# US_BB_SH.net
KiCad netlist of a schematic drawn in Altium Designer
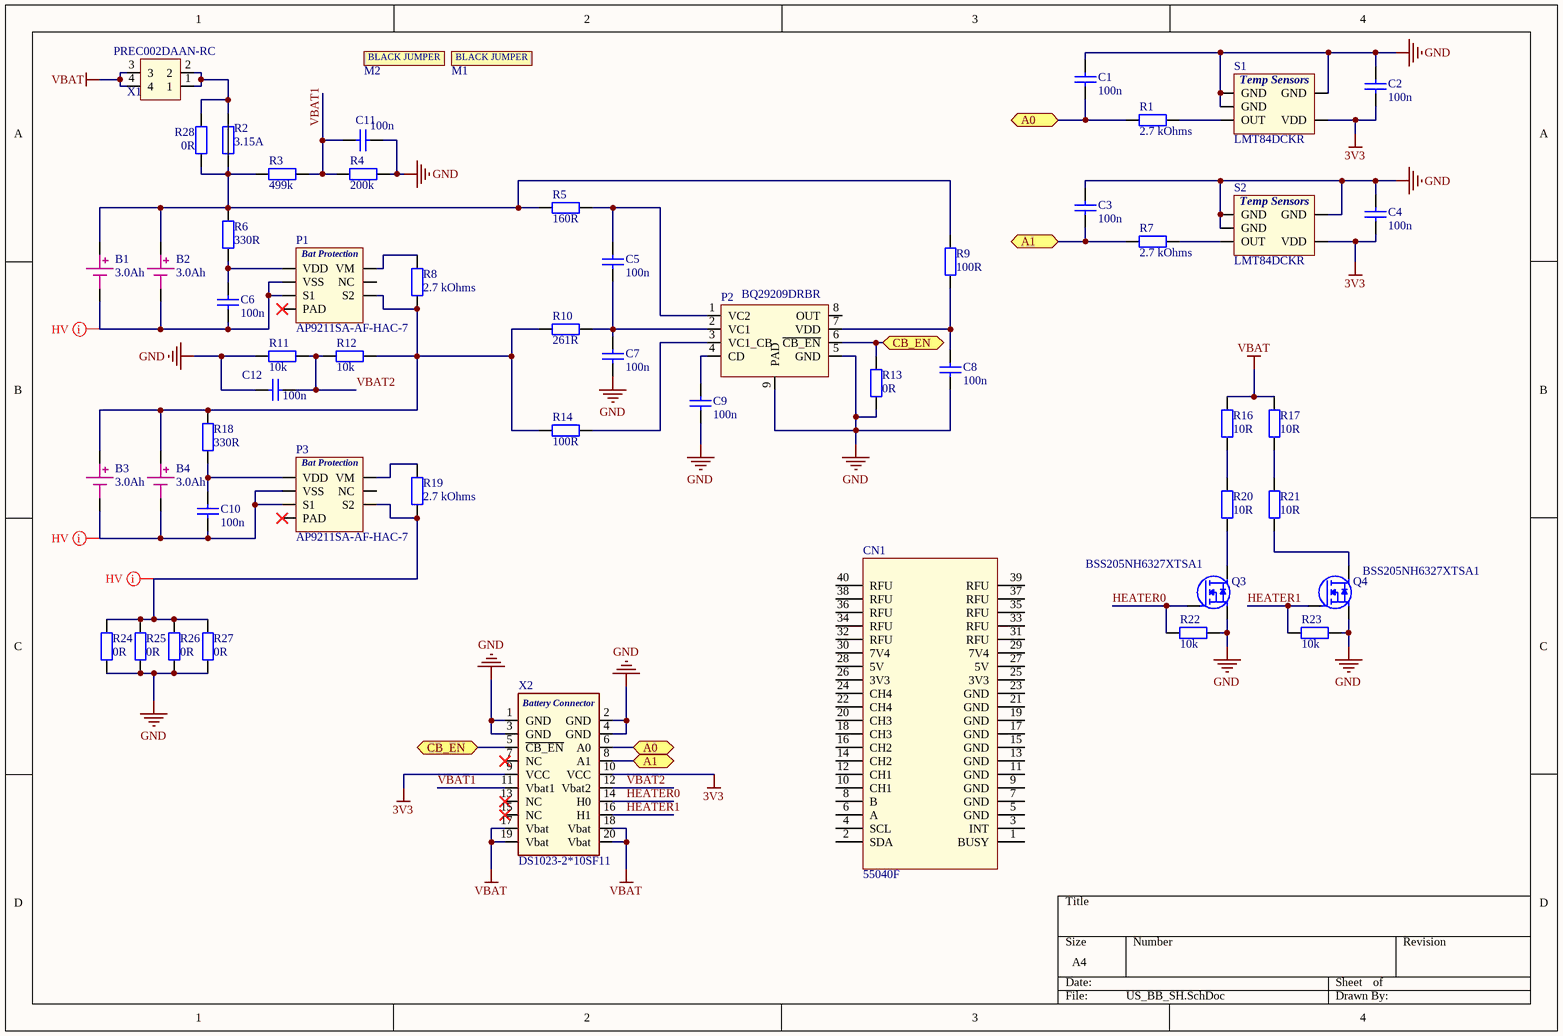
[diagram p0: US_BB_SH.SchDoc]

(export (version "E")
  (design (tool "Eeschema 10.0.6"))
  (components
    (comp (ref "B1")
      (value "3.0Ah")
      (footprint "BAT18650 1S-MSL")
      (description "18650 3.7V Lithium-Ion Battery Rechargeable (Secondary) 2.6Ah")
      (fields
        (field (name "MANUFACTURER") "Litokala")
        (field (name "MANUFACTURER PART NUMBER") "Litokala_HG2")
      )
      (libsource (lib "alfasat_lib_eps") (part "18650 3.7V Li-ion"))
    )
    (comp (ref "B2")
      (value "3.0Ah")
      (footprint "BAT18650 1S-MSL")
      (description "18650 3.7V Lithium-Ion Battery Rechargeable (Secondary) 2.6Ah")
      (fields
        (field (name "MANUFACTURER") "Litokala")
        (field (name "MANUFACTURER PART NUMBER") "Litokala_HG2")
      )
      (libsource (lib "alfasat_lib_eps") (part "18650 3.7V Li-ion"))
    )
    (comp (ref "B3")
      (value "3.0Ah")
      (footprint "BAT18650 1S-MSL")
      (description "18650 3.7V Lithium-Ion Battery Rechargeable (Secondary) 2.6Ah")
      (fields
        (field (name "MANUFACTURER") "Litokala")
        (field (name "MANUFACTURER PART NUMBER") "Litokala_HG2")
      )
      (libsource (lib "alfasat_lib_eps") (part "18650 3.7V Li-ion"))
    )
    (comp (ref "B4")
      (value "3.0Ah")
      (footprint "BAT18650 1S-MSL")
      (description "18650 3.7V Lithium-Ion Battery Rechargeable (Secondary) 2.6Ah")
      (fields
        (field (name "MANUFACTURER") "Litokala")
        (field (name "MANUFACTURER PART NUMBER") "Litokala_HG2")
      )
      (libsource (lib "alfasat_lib_eps") (part "18650 3.7V Li-ion"))
    )
    (comp (ref "C1")
      (value "100n")
      (footprint "C0603_IPC_HD")
      (description "CAP CER 0.1UF 16V X7R 0603")
      (fields
        (field (name "MANUFACTURER") "Samsung Electro-Mechanics")
        (field (name "MANUFACTURER PART NUMBER") "CL10B104KO8NNNC")
      )
      (libsource (lib "alfasat_lib") (part "CL10B104KO8NNNC"))
    )
    (comp (ref "C2")
      (value "100n")
      (footprint "C0603_IPC_HD")
      (description "CAP CER 0.1UF 16V X7R 0603")
      (fields
        (field (name "MANUFACTURER") "Samsung Electro-Mechanics")
        (field (name "MANUFACTURER PART NUMBER") "CL10B104KO8NNNC")
      )
      (libsource (lib "alfasat_lib") (part "CL10B104KO8NNNC"))
    )
    (comp (ref "C3")
      (value "100n")
      (footprint "C0603_IPC_HD")
      (description "CAP CER 0.1UF 16V X7R 0603")
      (fields
        (field (name "MANUFACTURER") "Samsung Electro-Mechanics")
        (field (name "MANUFACTURER PART NUMBER") "CL10B104KO8NNNC")
      )
      (libsource (lib "alfasat_lib") (part "CL10B104KO8NNNC"))
    )
    (comp (ref "C4")
      (value "100n")
      (footprint "C0603_IPC_HD")
      (description "CAP CER 0.1UF 16V X7R 0603")
      (fields
        (field (name "MANUFACTURER") "Samsung Electro-Mechanics")
        (field (name "MANUFACTURER PART NUMBER") "CL10B104KO8NNNC")
      )
      (libsource (lib "alfasat_lib") (part "CL10B104KO8NNNC"))
    )
    (comp (ref "C5")
      (value "100n")
      (footprint "C0603_IPC_HD")
      (description "CAP CER 0.1UF 16V X7R 0603")
      (fields
        (field (name "MANUFACTURER") "Samsung Electro-Mechanics")
        (field (name "MANUFACTURER PART NUMBER") "CL10B104KO8NNNC")
      )
      (libsource (lib "alfasat_lib") (part "CL10B104KO8NNNC"))
    )
    (comp (ref "C6")
      (value "100n")
      (footprint "C0603_IPC_HD")
      (description "CAP CER 0.1UF 16V X7R 0603")
      (fields
        (field (name "MANUFACTURER") "Samsung Electro-Mechanics")
        (field (name "MANUFACTURER PART NUMBER") "CL10B104KO8NNNC")
      )
      (libsource (lib "alfasat_lib") (part "CL10B104KO8NNNC"))
    )
    (comp (ref "C7")
      (value "100n")
      (footprint "C0603_IPC_HD")
      (description "CAP CER 0.1UF 16V X7R 0603")
      (fields
        (field (name "MANUFACTURER") "Samsung Electro-Mechanics")
        (field (name "MANUFACTURER PART NUMBER") "CL10B104KO8NNNC")
      )
      (libsource (lib "alfasat_lib") (part "CL10B104KO8NNNC"))
    )
    (comp (ref "C8")
      (value "100n")
      (footprint "C0603_IPC_HD")
      (description "CAP CER 0.1UF 16V X7R 0603")
      (fields
        (field (name "MANUFACTURER") "Samsung Electro-Mechanics")
        (field (name "MANUFACTURER PART NUMBER") "CL10B104KO8NNNC")
      )
      (libsource (lib "alfasat_lib") (part "CL10B104KO8NNNC"))
    )
    (comp (ref "C9")
      (value "100n")
      (footprint "C0603_IPC_HD")
      (description "CAP CER 0.1UF 16V X7R 0603")
      (fields
        (field (name "MANUFACTURER") "Samsung Electro-Mechanics")
        (field (name "MANUFACTURER PART NUMBER") "CL10B104KO8NNNC")
      )
      (libsource (lib "alfasat_lib") (part "CL10B104KO8NNNC"))
    )
    (comp (ref "C10")
      (value "100n")
      (footprint "C0603_IPC_HD")
      (description "CAP CER 0.1UF 16V X7R 0603")
      (fields
        (field (name "MANUFACTURER") "Samsung Electro-Mechanics")
        (field (name "MANUFACTURER PART NUMBER") "CL10B104KO8NNNC")
      )
      (libsource (lib "alfasat_lib") (part "CL10B104KO8NNNC"))
    )
    (comp (ref "C11")
      (value "100n")
      (footprint "C0603_IPC_HD")
      (description "CAP CER 0.1UF 16V X7R 0603")
      (fields
        (field (name "MANUFACTURER") "Samsung Electro-Mechanics")
        (field (name "MANUFACTURER PART NUMBER") "CL10B104KO8NNNC")
      )
      (libsource (lib "alfasat_parts_lib") (part "CL10B104KO8NNNC"))
    )
    (comp (ref "C12")
      (value "100n")
      (footprint "C0603_IPC_HD")
      (description "CAP CER 0.1UF 16V X7R 0603")
      (fields
        (field (name "MANUFACTURER") "Samsung Electro-Mechanics")
        (field (name "MANUFACTURER PART NUMBER") "CL10B104KO8NNNC")
      )
      (libsource (lib "alfasat_parts_lib") (part "CL10B104KO8NNNC"))
    )
    (comp (ref "CN1")
      (value "55040F")
      (footprint "HEADER_40PIN_12MM2")
      (description "CONN HEADER R/A 40POS 2.54MM")
      (fields (field (name "MANUFACTURER") "On Shore Technology Inc."))
      (libsource (lib "alfasat_lib") (part "ALFASAT_BIC"))
    )
    (comp (ref "M1")
      (value "STC02SYAN")
      (description "CONN JUMPER SHORTING TIN")
      (fields (field (name "MANUFACTURER") "Sullins Connector Solutions"))
      (libsource (lib "alfasat_lib") (part "STC02SYAN"))
    )
    (comp (ref "M2")
      (value "STC02SYAN")
      (description "CONN JUMPER SHORTING TIN")
      (fields (field (name "MANUFACTURER") "Sullins Connector Solutions"))
      (libsource (lib "alfasat_lib") (part "STC02SYAN"))
    )
    (comp (ref "P1")
      (value "AP9211SA-AF-HAC-7")
      (footprint "U-DFN2030-6 (Type C)")
      (description "Battery Battery Protection IC Lithium-Ion U-DFN2030-6 (Type C)")
      (fields (field (name "MANUFACTURER") "Diodes Incorporated"))
      (libsource (lib "alfasat_lib_eps") (part "AP9211SA-AF"))
    )
    (comp (ref "P2")
      (value "BQ29209DRBR")
      (footprint "alfasat_lib_eps:bq29209_SON65P300X100_HS-9N")
      (description "Battery Battery Protection IC Lithium-Ion 8-SON (3x3)")
      (fields (field (name "MANUFACTURER") "Texas Instruments"))
      (libsource (lib "alfasat_lib_eps") (part "BQ29209DRBR"))
    )
    (comp (ref "P3")
      (value "AP9211SA-AF-HAC-7")
      (footprint "U-DFN2030-6 (Type C)")
      (description "Battery Battery Protection IC Lithium-Ion U-DFN2030-6 (Type C)")
      (fields (field (name "MANUFACTURER") "Diodes Incorporated"))
      (libsource (lib "alfasat_lib_eps") (part "AP9211SA-AF"))
    )
    (comp (ref "Q3")
      (value "BSS205NH6327XTSA1")
      (footprint "SOT23")
      (description "N-Channel 20V 2.5A (Ta) 500mW (Ta) Surface Mount SOT-23-3")
      (fields (field (name "MANUFACTURER") "Infineon Technologies"))
      (libsource (lib "alfasat_lib_eps") (part "BSS205NH6327XTSA1"))
    )
    (comp (ref "Q4")
      (value "BSS205NH6327XTSA1")
      (footprint "SOT23")
      (description "N-Channel 20V 2.5A (Ta) 500mW (Ta) Surface Mount SOT-23-3")
      (fields (field (name "MANUFACTURER") "Infineon Technologies"))
      (libsource (lib "alfasat_lib_eps") (part "BSS205NH6327XTSA1"))
    )
    (comp (ref "R1")
      (value "2.7 kOhms")
      (footprint "alfasat_lib_eps:C0805_IPC_HD")
      (description "RES 2.7K OHM 1% 1/8W 0805")
      (fields
        (field (name "MANUFACTURER") "Stackpole Electronics Inc")
        (field (name "MANUFACTURER PART NUMBER") "RMCF0805FT2K70")
      )
      (libsource (lib "") (part "CR0805_RMC_2.7k_1"))
    )
    (comp (ref "R2")
      (value "3.15A")
      (footprint "alfasat_lib_eps:C0603_IPC_MD")
      (description "FUSE BOARD MNT 3.15A 32VDC 0603")
      (fields
        (field (name "MANUFACTURER") "Panasonic Electronic Components")
        (field (name "MANUFACTURER PART NUMBER") "ERB-RE3R15V")
      )
      (libsource (lib "alfasat_lib_eps") (part "CR0603_3A15"))
    )
    (comp (ref "R3")
      (value "499k")
      (footprint "alfasat_lib_eps:C0603_IPC_HD")
      (description "RES 499K OHM 1% 1/10W 0603")
      (fields
        (field (name "MANUFACTURER") "Stackpole Electronics Inc")
        (field (name "MANUFACTURER PART NUMBER") "RMCF0603FT499K")
      )
      (libsource (lib "alfasat_lib_eps") (part "CR0603-JW-499K"))
    )
    (comp (ref "R4")
      (value "200k")
      (footprint "alfasat_lib_eps:C0603_IPC_HD")
      (description "RES 200K OHM 1% 1/10W 0603")
      (fields
        (field (name "MANUFACTURER") "Stackpole Electronics Inc")
        (field (name "MANUFACTURER PART NUMBER") "RMCF0603FT200K")
      )
      (libsource (lib "alfasat_lib_eps") (part "CR0603-JW-200k"))
    )
    (comp (ref "R5")
      (value "160R")
      (footprint "C0805_IPC_HD")
      (description "RES SMD 160 OHM 1% 1/8W 0805")
      (fields
        (field (name "MANUFACTURER") "Rohm Semiconductor")
        (field (name "MANUFACTURER PART NUMBER") "MCR10ERTF1600")
      )
      (libsource (lib "alfasat_lib_eps") (part "CR0805_RMC_160R"))
    )
    (comp (ref "R6")
      (value "330R")
      (footprint "alfasat_lib_eps:C0805_IPC_HD")
      (description "RES 330 OHM 1% 1/8W 0805")
      (fields
        (field (name "MANUFACTURER") "Stackpole Electronics Inc")
        (field (name "MANUFACTURER PART NUMBER") "RMCF0805FT330R")
      )
      (libsource (lib "alfasat_lib_eps") (part "CR0805_RMC_330R"))
    )
    (comp (ref "R7")
      (value "2.7 kOhms")
      (footprint "alfasat_lib_eps:C0805_IPC_HD")
      (description "RES 2.7K OHM 1% 1/8W 0805")
      (fields
        (field (name "MANUFACTURER") "Stackpole Electronics Inc")
        (field (name "MANUFACTURER PART NUMBER") "RMCF0805FT2K70")
      )
      (libsource (lib "") (part "CR0805_RMC_2.7k_1"))
    )
    (comp (ref "R8")
      (value "2.7 kOhms")
      (footprint "alfasat_lib_eps:C0805_IPC_HD")
      (description "RES 2.7K OHM 1% 1/8W 0805")
      (fields
        (field (name "MANUFACTURER") "Stackpole Electronics Inc")
        (field (name "MANUFACTURER PART NUMBER") "RMCF0805FT2K70")
      )
      (libsource (lib "alfasat_lib_eps") (part "CR0805_RMC_2.7k"))
    )
    (comp (ref "R9")
      (value "100R")
      (footprint "R0805_IPC_MD")
      (description "RES 100 OHM 1% 1/8W 0805")
      (fields
        (field (name "MANUFACTURER") "Stackpole Electronics Inc")
        (field (name "MANUFACTURER PART NUMBER") "RMCF0805FT100R")
      )
      (libsource (lib "alfasat_lib_eps") (part "CR0805_RMC1_100R"))
    )
    (comp (ref "R10")
      (value "261R")
      (footprint "C0805_IPC_HD")
      (description "RES SMD 261 OHM 1% 1/8W 0805")
      (fields
        (field (name "MANUFACTURER") "Rohm Semiconductor")
        (field (name "MANUFACTURER PART NUMBER") "MCR10ERTF2610")
      )
      (libsource (lib "alfasat_lib_eps") (part "CR0805_RMC_261R"))
    )
    (comp (ref "R11")
      (value "10k")
      (footprint "C0603_IPC_HD")
      (description "RES 10K OHM 1% 1/10W 0603")
      (fields
        (field (name "MANUFACTURER") "Stackpole Electronics Inc")
        (field (name "MANUFACTURER PART NUMBER") "RMCF0603FT10K0")
      )
      (libsource (lib "alfasat_lib_eps") (part "CR0603-JW-10k"))
    )
    (comp (ref "R12")
      (value "10k")
      (footprint "C0603_IPC_HD")
      (description "RES 10K OHM 1% 1/10W 0603")
      (fields
        (field (name "MANUFACTURER") "Stackpole Electronics Inc")
        (field (name "MANUFACTURER PART NUMBER") "RMCF0603FT10K0")
      )
      (libsource (lib "alfasat_lib_eps") (part "CR0603-JW-10k"))
    )
    (comp (ref "R13")
      (value "0R")
      (footprint "R0603_IPC_MD")
      (description "RES SMD 0 OHM JUMPER 1/10W 0603")
      (fields
        (field (name "MANUFACTURER") "Bourns Inc.")
        (field (name "MANUFACTURER PART NUMBER") "CR0603-J/-000ELF")
      )
      (libsource (lib "alfasat_lib") (part "CR0603-J/-000ELF"))
    )
    (comp (ref "R14")
      (value "100R")
      (footprint "R0805_IPC_MD")
      (description "RES 100 OHM 1% 1/8W 0805")
      (fields
        (field (name "MANUFACTURER") "Stackpole Electronics Inc")
        (field (name "MANUFACTURER PART NUMBER") "RMCF0805FT100R")
      )
      (libsource (lib "") (part "CR0805_RMC1_100R_1"))
    )
    (comp (ref "R16")
      (value "10R")
      (footprint "alfasat_lib_eps:FMP300JT-73-10R")
      (description "RES 10 OHM 3W 5% AXIAL")
      (fields
        (field (name "MANUFACTURER") "Yageo")
        (field (name "MANUFACTURER PART NUMBER") "FMP300JT-73-10R")
      )
      (libsource (lib "alfasat_lib_eps") (part "FMP300JT-73-10R"))
    )
    (comp (ref "R17")
      (value "10R")
      (footprint "alfasat_lib_eps:FMP300JT-73-10R")
      (description "RES 10 OHM 3W 5% AXIAL")
      (fields
        (field (name "MANUFACTURER") "Yageo")
        (field (name "MANUFACTURER PART NUMBER") "FMP300JT-73-10R")
      )
      (libsource (lib "alfasat_lib_eps") (part "FMP300JT-73-10R"))
    )
    (comp (ref "R18")
      (value "330R")
      (footprint "alfasat_lib_eps:C0805_IPC_HD")
      (description "RES 330 OHM 1% 1/8W 0805")
      (fields
        (field (name "MANUFACTURER") "Stackpole Electronics Inc")
        (field (name "MANUFACTURER PART NUMBER") "RMCF0805FT330R")
      )
      (libsource (lib "alfasat_lib_eps") (part "CR0805_RMC_330R"))
    )
    (comp (ref "R19")
      (value "2.7 kOhms")
      (footprint "alfasat_lib_eps:C0805_IPC_HD")
      (description "RES 2.7K OHM 1% 1/8W 0805")
      (fields
        (field (name "MANUFACTURER") "Stackpole Electronics Inc")
        (field (name "MANUFACTURER PART NUMBER") "RMCF0805FT2K70")
      )
      (libsource (lib "alfasat_lib_eps") (part "CR0805_RMC_2.7k"))
    )
    (comp (ref "R20")
      (value "10R")
      (footprint "alfasat_lib_eps:FMP300JT-73-10R")
      (description "RES 10 OHM 3W 5% AXIAL")
      (fields
        (field (name "MANUFACTURER") "Yageo")
        (field (name "MANUFACTURER PART NUMBER") "FMP300JT-73-10R")
      )
      (libsource (lib "alfasat_lib_eps") (part "FMP300JT-73-10R"))
    )
    (comp (ref "R21")
      (value "10R")
      (footprint "alfasat_lib_eps:FMP300JT-73-10R")
      (description "RES 10 OHM 3W 5% AXIAL")
      (fields
        (field (name "MANUFACTURER") "Yageo")
        (field (name "MANUFACTURER PART NUMBER") "FMP300JT-73-10R")
      )
      (libsource (lib "alfasat_lib_eps") (part "FMP300JT-73-10R"))
    )
    (comp (ref "R22")
      (value "10k")
      (footprint "C0603_IPC_HD")
      (description "RES 10K OHM 1% 1/10W 0603")
      (fields
        (field (name "MANUFACTURER") "Stackpole Electronics Inc")
        (field (name "MANUFACTURER PART NUMBER") "RMCF0603FT10K0")
      )
      (libsource (lib "") (part "CR0603-JW-10k_1"))
    )
    (comp (ref "R23")
      (value "10k")
      (footprint "C0603_IPC_HD")
      (description "RES 10K OHM 1% 1/10W 0603")
      (fields
        (field (name "MANUFACTURER") "Stackpole Electronics Inc")
        (field (name "MANUFACTURER PART NUMBER") "RMCF0603FT10K0")
      )
      (libsource (lib "alfasat_lib_eps") (part "CR0603-JW-10k"))
    )
    (comp (ref "R24")
      (value "0R")
      (footprint "R0603_IPC_MD")
      (description "RES SMD 0 OHM JUMPER 1/10W 0603")
      (fields
        (field (name "MANUFACTURER") "Bourns Inc.")
        (field (name "MANUFACTURER PART NUMBER") "CR0603-J/-000ELF")
      )
      (libsource (lib "alfasat_lib") (part "CR0603-J/-000ELF"))
    )
    (comp (ref "R25")
      (value "0R")
      (footprint "R0603_IPC_MD")
      (description "RES SMD 0 OHM JUMPER 1/10W 0603")
      (fields
        (field (name "MANUFACTURER") "Bourns Inc.")
        (field (name "MANUFACTURER PART NUMBER") "CR0603-J/-000ELF")
      )
      (libsource (lib "alfasat_lib") (part "CR0603-J/-000ELF"))
    )
    (comp (ref "R26")
      (value "0R")
      (footprint "R0603_IPC_MD")
      (description "RES SMD 0 OHM JUMPER 1/10W 0603")
      (fields
        (field (name "MANUFACTURER") "Bourns Inc.")
        (field (name "MANUFACTURER PART NUMBER") "CR0603-J/-000ELF")
      )
      (libsource (lib "alfasat_lib") (part "CR0603-J/-000ELF"))
    )
    (comp (ref "R27")
      (value "0R")
      (footprint "R0603_IPC_MD")
      (description "RES SMD 0 OHM JUMPER 1/10W 0603")
      (fields
        (field (name "MANUFACTURER") "Bourns Inc.")
        (field (name "MANUFACTURER PART NUMBER") "CR0603-J/-000ELF")
      )
      (libsource (lib "alfasat_lib") (part "CR0603-J/-000ELF"))
    )
    (comp (ref "R28")
      (value "0R")
      (footprint "R0603_IPC_MD")
      (description "RES SMD 0 OHM JUMPER 1/10W 0603")
      (fields
        (field (name "MANUFACTURER") "Bourns Inc.")
        (field (name "MANUFACTURER PART NUMBER") "CR0603-J/-000ELF")
      )
      (libsource (lib "alfasat_lib") (part "CR0603-J/-000ELF"))
    )
    (comp (ref "S1")
      (value "LMT84DCKR")
      (footprint "alfasat_lib_eps:LMT84DCKR_SOT65P210X110-5N")
      (description "Temperature Sensor Analog, Local -50°C ~ 150°C 5.5mV/°C SC-70-5")
      (fields (field (name "MANUFACTURER") "Texas Instruments"))
      (libsource (lib "alfasat_lib_eps") (part "LMT84DCKR"))
    )
    (comp (ref "S2")
      (value "LMT84DCKR")
      (footprint "alfasat_lib_eps:LMT84DCKR_SOT65P210X110-5N")
      (description "Temperature Sensor Analog, Local -50°C ~ 150°C 5.5mV/°C SC-70-5")
      (fields (field (name "MANUFACTURER") "Texas Instruments"))
      (libsource (lib "alfasat_lib_eps") (part "LMT84DCKR"))
    )
    (comp (ref "X1")
      (value "PREC002DAAN-RC")
      (footprint "GPLD_2X2")
      (description "Connector Header Through Hole 4 position 0.100\" (2.54mm)")
      (fields (field (name "MANUFACTURER") "Sullins Connector Solutions"))
      (libsource (lib "alfasat_lib_eps") (part "PLD_2X2"))
    )
    (comp (ref "X2")
      (value "DS1023-2*10SF11")
      (footprint "ESQ-110-33-T-D")
      (description "20 Position Elevated Socket Connector  Through Hole")
      (fields (field (name "MANUFACTURER") "CONNFLY Elec"))
      (libsource (lib "alfasat_lib_eps") (part "DS1023-2*10SF11"))
    )
  )
  (nets
    (net (code "1") (name "/A0") (class "Default")
      (node (ref "C1") (pin "1") (pinfunction "1_1") (pintype "passive"))
      (node (ref "R1") (pin "1") (pinfunction "1_1") (pintype "passive"))
      (node (ref "X2") (pin "6") (pinfunction "A0_6") (pintype "passive"))
    )
    (net (code "2") (name "/A1") (class "Default")
      (node (ref "C3") (pin "1") (pinfunction "1_1") (pintype "passive"))
      (node (ref "R7") (pin "1") (pinfunction "1_1") (pintype "passive"))
      (node (ref "X2") (pin "8") (pinfunction "A1_8") (pintype "passive"))
    )
    (net (code "3") (name "/CB_EN") (class "Default")
      (node (ref "P2") (pin "6") (pinfunction "~{CB_EN}_6") (pintype "passive"))
      (node (ref "R13") (pin "2") (pinfunction "2_2") (pintype "passive"))
      (node (ref "X2") (pin "5") (pinfunction "~{CB_EN}_5") (pintype "passive"))
    )
    (net (code "4") (name "/HEATER0") (class "Default")
      (node (ref "Q3") (pin "1") (pinfunction "G_1") (pintype "passive"))
      (node (ref "R22") (pin "2") (pinfunction "2_2") (pintype "passive"))
      (node (ref "X2") (pin "14") (pinfunction "H0_14") (pintype "passive"))
    )
    (net (code "5") (name "/HEATER1") (class "Default")
      (node (ref "Q4") (pin "1") (pinfunction "G_1") (pintype "passive"))
      (node (ref "R23") (pin "1") (pinfunction "1_1") (pintype "passive"))
      (node (ref "X2") (pin "16") (pinfunction "H1_16") (pintype "passive"))
    )
    (net (code "6") (name "/VBAT1") (class "Default")
      (node (ref "C11") (pin "1") (pinfunction "1_1") (pintype "passive"))
      (node (ref "R3") (pin "2") (pinfunction "2_2") (pintype "passive"))
      (node (ref "R4") (pin "1") (pinfunction "1_1") (pintype "passive"))
      (node (ref "X2") (pin "11") (pinfunction "Vbat1_11") (pintype "passive"))
    )
    (net (code "7") (name "/VBAT2") (class "Default")
      (node (ref "C12") (pin "2") (pinfunction "2_2") (pintype "passive"))
      (node (ref "R11") (pin "2") (pinfunction "2_2") (pintype "passive"))
      (node (ref "R12") (pin "1") (pinfunction "1_1") (pintype "passive"))
      (node (ref "X2") (pin "12") (pinfunction "Vbat2_12") (pintype "passive"))
    )
    (net (code "8") (name "3V3") (class "Default")
      (node (ref "C2") (pin "1") (pinfunction "1_1") (pintype "passive"))
      (node (ref "C4") (pin "1") (pinfunction "1_1") (pintype "passive"))
      (node (ref "S1") (pin "4") (pinfunction "VDD_4") (pintype "passive"))
      (node (ref "S2") (pin "4") (pinfunction "VDD_4") (pintype "passive"))
      (node (ref "X2") (pin "10") (pinfunction "VCC_10") (pintype "passive"))
      (node (ref "X2") (pin "9") (pinfunction "VCC_9") (pintype "passive"))
    )
    (net (code "9") (name "GND") (class "Default")
      (node (ref "C1") (pin "2") (pinfunction "2_2") (pintype "passive"))
      (node (ref "C11") (pin "2") (pinfunction "2_2") (pintype "passive"))
      (node (ref "C12") (pin "1") (pinfunction "1_1") (pintype "passive"))
      (node (ref "C2") (pin "2") (pinfunction "2_2") (pintype "passive"))
      (node (ref "C3") (pin "2") (pinfunction "2_2") (pintype "passive"))
      (node (ref "C4") (pin "2") (pinfunction "2_2") (pintype "passive"))
      (node (ref "C7") (pin "1") (pinfunction "1_1") (pintype "passive"))
      (node (ref "C8") (pin "1") (pinfunction "1_1") (pintype "passive"))
      (node (ref "C9") (pin "1") (pinfunction "1_1") (pintype "passive"))
      (node (ref "P2") (pin "5") (pinfunction "GND_5") (pintype "passive"))
      (node (ref "P2") (pin "9") (pinfunction "PAD_9") (pintype "passive"))
      (node (ref "Q3") (pin "2") (pinfunction "S_2") (pintype "passive"))
      (node (ref "Q4") (pin "2") (pinfunction "S_2") (pintype "passive"))
      (node (ref "R11") (pin "1") (pinfunction "1_1") (pintype "passive"))
      (node (ref "R13") (pin "1") (pinfunction "1_1") (pintype "passive"))
      (node (ref "R22") (pin "1") (pinfunction "1_1") (pintype "passive"))
      (node (ref "R23") (pin "2") (pinfunction "2_2") (pintype "passive"))
      (node (ref "R24") (pin "1") (pinfunction "1_1") (pintype "passive"))
      (node (ref "R25") (pin "1") (pinfunction "1_1") (pintype "passive"))
      (node (ref "R26") (pin "1") (pinfunction "1_1") (pintype "passive"))
      (node (ref "R27") (pin "1") (pinfunction "1_1") (pintype "passive"))
      (node (ref "R4") (pin "2") (pinfunction "2_2") (pintype "passive"))
      (node (ref "S1") (pin "1") (pinfunction "GND_1") (pintype "passive"))
      (node (ref "S1") (pin "2") (pinfunction "GND_2") (pintype "passive"))
      (node (ref "S1") (pin "5") (pinfunction "GND_5") (pintype "passive"))
      (node (ref "S2") (pin "1") (pinfunction "GND_1") (pintype "passive"))
      (node (ref "S2") (pin "2") (pinfunction "GND_2") (pintype "passive"))
      (node (ref "S2") (pin "5") (pinfunction "GND_5") (pintype "passive"))
      (node (ref "X2") (pin "1") (pinfunction "GND_1") (pintype "passive"))
      (node (ref "X2") (pin "2") (pinfunction "GND_2") (pintype "passive"))
      (node (ref "X2") (pin "3") (pinfunction "GND_3") (pintype "passive"))
      (node (ref "X2") (pin "4") (pinfunction "GND_4") (pintype "passive"))
    )
    (net (code "10") (name "Net-(B1-Pad1)") (class "Default")
      (node (ref "B1") (pin "1") (pinfunction "1_1") (pintype "passive"))
      (node (ref "B2") (pin "1") (pinfunction "1_1") (pintype "passive"))
      (node (ref "R2") (pin "1") (pinfunction "1_1") (pintype "passive"))
      (node (ref "R28") (pin "1") (pinfunction "1_1") (pintype "passive"))
      (node (ref "R3") (pin "1") (pinfunction "1_1") (pintype "passive"))
      (node (ref "R5") (pin "1") (pinfunction "1_1") (pintype "passive"))
      (node (ref "R6") (pin "2") (pinfunction "2_2") (pintype "passive"))
      (node (ref "R9") (pin "2") (pinfunction "2_2") (pintype "passive"))
    )
    (net (code "11") (name "Net-(P1-S1)") (class "Default")
      (node (ref "B1") (pin "2") (pinfunction "2_2") (pintype "passive"))
      (node (ref "B2") (pin "2") (pinfunction "2_2") (pintype "passive"))
      (node (ref "C6") (pin "1") (pinfunction "1_1") (pintype "passive"))
      (node (ref "P1") (pin "1") (pinfunction "S1_1") (pintype "passive"))
      (node (ref "P1") (pin "2") (pinfunction "VSS_2") (pintype "passive"))
    )
    (net (code "12") (name "Net-(P1-S2)") (class "Default")
      (node (ref "B3") (pin "1") (pinfunction "1_1") (pintype "passive"))
      (node (ref "B4") (pin "1") (pinfunction "1_1") (pintype "passive"))
      (node (ref "P1") (pin "6") (pinfunction "S2_6") (pintype "passive"))
      (node (ref "R10") (pin "1") (pinfunction "1_1") (pintype "passive"))
      (node (ref "R12") (pin "2") (pinfunction "2_2") (pintype "passive"))
      (node (ref "R14") (pin "2") (pinfunction "2_2") (pintype "passive"))
      (node (ref "R18") (pin "2") (pinfunction "2_2") (pintype "passive"))
      (node (ref "R8") (pin "1") (pinfunction "1_1") (pintype "passive"))
    )
    (net (code "13") (name "Net-(P1-VDD)") (class "Default")
      (node (ref "C6") (pin "2") (pinfunction "2_2") (pintype "passive"))
      (node (ref "P1") (pin "3") (pinfunction "VDD_3") (pintype "passive"))
      (node (ref "R6") (pin "1") (pinfunction "1_1") (pintype "passive"))
    )
    (net (code "14") (name "Net-(P1-VM)") (class "Default")
      (node (ref "P1") (pin "5") (pinfunction "VM_5") (pintype "passive"))
      (node (ref "R8") (pin "2") (pinfunction "2_2") (pintype "passive"))
    )
    (net (code "15") (name "Net-(P2-CD)") (class "Default")
      (node (ref "C9") (pin "2") (pinfunction "2_2") (pintype "passive"))
      (node (ref "P2") (pin "4") (pinfunction "CD_4") (pintype "passive"))
    )
    (net (code "16") (name "Net-(P2-VC1)") (class "Default")
      (node (ref "C5") (pin "1") (pinfunction "1_1") (pintype "passive"))
      (node (ref "C7") (pin "2") (pinfunction "2_2") (pintype "passive"))
      (node (ref "P2") (pin "2") (pinfunction "VC1_2") (pintype "passive"))
      (node (ref "R10") (pin "2") (pinfunction "2_2") (pintype "passive"))
    )
    (net (code "17") (name "Net-(P2-VC1_CB)") (class "Default")
      (node (ref "P2") (pin "3") (pinfunction "VC1_CB_3") (pintype "passive"))
      (node (ref "R14") (pin "1") (pinfunction "1_1") (pintype "passive"))
    )
    (net (code "18") (name "Net-(P2-VC2)") (class "Default")
      (node (ref "C5") (pin "2") (pinfunction "2_2") (pintype "passive"))
      (node (ref "P2") (pin "1") (pinfunction "VC2_1") (pintype "passive"))
      (node (ref "R5") (pin "2") (pinfunction "2_2") (pintype "passive"))
    )
    (net (code "19") (name "Net-(P2-VDD)") (class "Default")
      (node (ref "C8") (pin "2") (pinfunction "2_2") (pintype "passive"))
      (node (ref "P2") (pin "7") (pinfunction "VDD_7") (pintype "passive"))
      (node (ref "R9") (pin "1") (pinfunction "1_1") (pintype "passive"))
    )
    (net (code "20") (name "Net-(P3-S1)") (class "Default")
      (node (ref "B3") (pin "2") (pinfunction "2_2") (pintype "passive"))
      (node (ref "B4") (pin "2") (pinfunction "2_2") (pintype "passive"))
      (node (ref "C10") (pin "1") (pinfunction "1_1") (pintype "passive"))
      (node (ref "P3") (pin "1") (pinfunction "S1_1") (pintype "passive"))
      (node (ref "P3") (pin "2") (pinfunction "VSS_2") (pintype "passive"))
    )
    (net (code "21") (name "Net-(P3-S2)") (class "Default")
      (node (ref "P3") (pin "6") (pinfunction "S2_6") (pintype "passive"))
      (node (ref "R19") (pin "1") (pinfunction "1_1") (pintype "passive"))
      (node (ref "R24") (pin "2") (pinfunction "2_2") (pintype "passive"))
      (node (ref "R25") (pin "2") (pinfunction "2_2") (pintype "passive"))
      (node (ref "R26") (pin "2") (pinfunction "2_2") (pintype "passive"))
      (node (ref "R27") (pin "2") (pinfunction "2_2") (pintype "passive"))
    )
    (net (code "22") (name "Net-(P3-VDD)") (class "Default")
      (node (ref "C10") (pin "2") (pinfunction "2_2") (pintype "passive"))
      (node (ref "P3") (pin "3") (pinfunction "VDD_3") (pintype "passive"))
      (node (ref "R18") (pin "1") (pinfunction "1_1") (pintype "passive"))
    )
    (net (code "23") (name "Net-(P3-VM)") (class "Default")
      (node (ref "P3") (pin "5") (pinfunction "VM_5") (pintype "passive"))
      (node (ref "R19") (pin "2") (pinfunction "2_2") (pintype "passive"))
    )
    (net (code "24") (name "Net-(Q3-D)") (class "Default")
      (node (ref "Q3") (pin "3") (pinfunction "D_3") (pintype "passive"))
      (node (ref "R20") (pin "1") (pinfunction "1_1") (pintype "passive"))
    )
    (net (code "25") (name "Net-(Q4-D)") (class "Default")
      (node (ref "Q4") (pin "3") (pinfunction "D_3") (pintype "passive"))
      (node (ref "R21") (pin "1") (pinfunction "1_1") (pintype "passive"))
    )
    (net (code "26") (name "Net-(R2-Pad2)") (class "Default")
      (node (ref "R2") (pin "2") (pinfunction "2_2") (pintype "passive"))
      (node (ref "R28") (pin "2") (pinfunction "2_2") (pintype "passive"))
      (node (ref "X1") (pin "1") (pinfunction "1_1") (pintype "passive"))
      (node (ref "X1") (pin "2") (pinfunction "2_2") (pintype "passive"))
    )
    (net (code "27") (name "Net-(R16-Pad1)") (class "Default")
      (node (ref "R16") (pin "1") (pinfunction "1_1") (pintype "passive"))
      (node (ref "R20") (pin "2") (pinfunction "2_2") (pintype "passive"))
    )
    (net (code "28") (name "Net-(R17-Pad1)") (class "Default")
      (node (ref "R17") (pin "1") (pinfunction "1_1") (pintype "passive"))
      (node (ref "R21") (pin "2") (pinfunction "2_2") (pintype "passive"))
    )
    (net (code "29") (name "Net-(S1-OUT)") (class "Default")
      (node (ref "R1") (pin "2") (pinfunction "2_2") (pintype "passive"))
      (node (ref "S1") (pin "3") (pinfunction "OUT_3") (pintype "passive"))
    )
    (net (code "30") (name "Net-(S2-OUT)") (class "Default")
      (node (ref "R7") (pin "2") (pinfunction "2_2") (pintype "passive"))
      (node (ref "S2") (pin "3") (pinfunction "OUT_3") (pintype "passive"))
    )
    (net (code "31") (name "VBAT") (class "Default")
      (node (ref "R16") (pin "2") (pinfunction "2_2") (pintype "passive"))
      (node (ref "R17") (pin "2") (pinfunction "2_2") (pintype "passive"))
      (node (ref "X1") (pin "3") (pinfunction "3_3") (pintype "passive"))
      (node (ref "X1") (pin "4") (pinfunction "4_4") (pintype "passive"))
      (node (ref "X2") (pin "17") (pinfunction "Vbat_17") (pintype "passive"))
      (node (ref "X2") (pin "18") (pinfunction "Vbat_18") (pintype "passive"))
      (node (ref "X2") (pin "19") (pinfunction "Vbat_19") (pintype "passive"))
      (node (ref "X2") (pin "20") (pinfunction "Vbat_20") (pintype "passive"))
    )
    (net (code "32") (name "unconnected-(CN1-3V3-Pad25)") (class "Default")
      (node (ref "CN1") (pin "25") (pinfunction "3V3_25") (pintype "passive"))
    )
    (net (code "33") (name "unconnected-(CN1-3V3-Pad26)") (class "Default")
      (node (ref "CN1") (pin "26") (pinfunction "3V3_26") (pintype "passive"))
    )
    (net (code "34") (name "unconnected-(CN1-5V-Pad27)") (class "Default")
      (node (ref "CN1") (pin "27") (pinfunction "5V_27") (pintype "passive"))
    )
    (net (code "35") (name "unconnected-(CN1-5V-Pad28)") (class "Default")
      (node (ref "CN1") (pin "28") (pinfunction "5V_28") (pintype "passive"))
    )
    (net (code "36") (name "unconnected-(CN1-7V4-Pad29)") (class "Default")
      (node (ref "CN1") (pin "29") (pinfunction "7V4_29") (pintype "passive"))
    )
    (net (code "37") (name "unconnected-(CN1-7V4-Pad30)") (class "Default")
      (node (ref "CN1") (pin "30") (pinfunction "7V4_30") (pintype "passive"))
    )
    (net (code "38") (name "unconnected-(CN1-A-Pad6)") (class "Default")
      (node (ref "CN1") (pin "6") (pinfunction "A_6") (pintype "passive"))
    )
    (net (code "39") (name "unconnected-(CN1-B-Pad8)") (class "Default")
      (node (ref "CN1") (pin "8") (pinfunction "B_8") (pintype "passive"))
    )
    (net (code "40") (name "unconnected-(CN1-BUSY-Pad1)") (class "Default")
      (node (ref "CN1") (pin "1") (pinfunction "BUSY_1") (pintype "passive"))
    )
    (net (code "41") (name "unconnected-(CN1-CH1-Pad10)") (class "Default")
      (node (ref "CN1") (pin "10") (pinfunction "CH1_10") (pintype "passive"))
    )
    (net (code "42") (name "unconnected-(CN1-CH1-Pad12)") (class "Default")
      (node (ref "CN1") (pin "12") (pinfunction "CH1_12") (pintype "passive"))
    )
    (net (code "43") (name "unconnected-(CN1-CH2-Pad14)") (class "Default")
      (node (ref "CN1") (pin "14") (pinfunction "CH2_14") (pintype "passive"))
    )
    (net (code "44") (name "unconnected-(CN1-CH2-Pad16)") (class "Default")
      (node (ref "CN1") (pin "16") (pinfunction "CH2_16") (pintype "passive"))
    )
    (net (code "45") (name "unconnected-(CN1-CH3-Pad18)") (class "Default")
      (node (ref "CN1") (pin "18") (pinfunction "CH3_18") (pintype "passive"))
    )
    (net (code "46") (name "unconnected-(CN1-CH3-Pad20)") (class "Default")
      (node (ref "CN1") (pin "20") (pinfunction "CH3_20") (pintype "passive"))
    )
    (net (code "47") (name "unconnected-(CN1-CH4-Pad22)") (class "Default")
      (node (ref "CN1") (pin "22") (pinfunction "CH4_22") (pintype "passive"))
    )
    (net (code "48") (name "unconnected-(CN1-CH4-Pad24)") (class "Default")
      (node (ref "CN1") (pin "24") (pinfunction "CH4_24") (pintype "passive"))
    )
    (net (code "49") (name "unconnected-(CN1-GND-Pad5)") (class "Default")
      (node (ref "CN1") (pin "5") (pinfunction "GND_5") (pintype "passive"))
    )
    (net (code "50") (name "unconnected-(CN1-GND-Pad7)") (class "Default")
      (node (ref "CN1") (pin "7") (pinfunction "GND_7") (pintype "passive"))
    )
    (net (code "51") (name "unconnected-(CN1-GND-Pad9)") (class "Default")
      (node (ref "CN1") (pin "9") (pinfunction "GND_9") (pintype "passive"))
    )
    (net (code "52") (name "unconnected-(CN1-GND-Pad11)") (class "Default")
      (node (ref "CN1") (pin "11") (pinfunction "GND_11") (pintype "passive"))
    )
    (net (code "53") (name "unconnected-(CN1-GND-Pad13)") (class "Default")
      (node (ref "CN1") (pin "13") (pinfunction "GND_13") (pintype "passive"))
    )
    (net (code "54") (name "unconnected-(CN1-GND-Pad15)") (class "Default")
      (node (ref "CN1") (pin "15") (pinfunction "GND_15") (pintype "passive"))
    )
    (net (code "55") (name "unconnected-(CN1-GND-Pad17)") (class "Default")
      (node (ref "CN1") (pin "17") (pinfunction "GND_17") (pintype "passive"))
    )
    (net (code "56") (name "unconnected-(CN1-GND-Pad19)") (class "Default")
      (node (ref "CN1") (pin "19") (pinfunction "GND_19") (pintype "passive"))
    )
    (net (code "57") (name "unconnected-(CN1-GND-Pad21)") (class "Default")
      (node (ref "CN1") (pin "21") (pinfunction "GND_21") (pintype "passive"))
    )
    (net (code "58") (name "unconnected-(CN1-GND-Pad23)") (class "Default")
      (node (ref "CN1") (pin "23") (pinfunction "GND_23") (pintype "passive"))
    )
    (net (code "59") (name "unconnected-(CN1-INT-Pad3)") (class "Default")
      (node (ref "CN1") (pin "3") (pinfunction "INT_3") (pintype "passive"))
    )
    (net (code "60") (name "unconnected-(CN1-RFU-Pad31)") (class "Default")
      (node (ref "CN1") (pin "31") (pinfunction "RFU_31") (pintype "passive"))
    )
    (net (code "61") (name "unconnected-(CN1-RFU-Pad32)") (class "Default")
      (node (ref "CN1") (pin "32") (pinfunction "RFU_32") (pintype "passive"))
    )
    (net (code "62") (name "unconnected-(CN1-RFU-Pad33)") (class "Default")
      (node (ref "CN1") (pin "33") (pinfunction "RFU_33") (pintype "passive"))
    )
    (net (code "63") (name "unconnected-(CN1-RFU-Pad34)") (class "Default")
      (node (ref "CN1") (pin "34") (pinfunction "RFU_34") (pintype "passive"))
    )
    (net (code "64") (name "unconnected-(CN1-RFU-Pad35)") (class "Default")
      (node (ref "CN1") (pin "35") (pinfunction "RFU_35") (pintype "passive"))
    )
    (net (code "65") (name "unconnected-(CN1-RFU-Pad36)") (class "Default")
      (node (ref "CN1") (pin "36") (pinfunction "RFU_36") (pintype "passive"))
    )
    (net (code "66") (name "unconnected-(CN1-RFU-Pad37)") (class "Default")
      (node (ref "CN1") (pin "37") (pinfunction "RFU_37") (pintype "passive"))
    )
    (net (code "67") (name "unconnected-(CN1-RFU-Pad38)") (class "Default")
      (node (ref "CN1") (pin "38") (pinfunction "RFU_38") (pintype "passive"))
    )
    (net (code "68") (name "unconnected-(CN1-RFU-Pad39)") (class "Default")
      (node (ref "CN1") (pin "39") (pinfunction "RFU_39") (pintype "passive"))
    )
    (net (code "69") (name "unconnected-(CN1-RFU-Pad40)") (class "Default")
      (node (ref "CN1") (pin "40") (pinfunction "RFU_40") (pintype "passive"))
    )
    (net (code "70") (name "unconnected-(CN1-SCL-Pad4)") (class "Default")
      (node (ref "CN1") (pin "4") (pinfunction "SCL_4") (pintype "passive"))
    )
    (net (code "71") (name "unconnected-(CN1-SDA-Pad2)") (class "Default")
      (node (ref "CN1") (pin "2") (pinfunction "SDA_2") (pintype "passive"))
    )
    (net (code "72") (name "unconnected-(P1-NC-Pad4)") (class "Default")
      (node (ref "P1") (pin "4") (pinfunction "NC_4") (pintype "passive"))
    )
    (net (code "73") (name "unconnected-(P1-PAD-Pad7)") (class "Default")
      (node (ref "P1") (pin "7") (pinfunction "PAD_7") (pintype "passive+no_connect"))
    )
    (net (code "74") (name "unconnected-(P2-OUT-Pad8)") (class "Default")
      (node (ref "P2") (pin "8") (pinfunction "OUT_8") (pintype "passive"))
    )
    (net (code "75") (name "unconnected-(P3-NC-Pad4)") (class "Default")
      (node (ref "P3") (pin "4") (pinfunction "NC_4") (pintype "passive"))
    )
    (net (code "76") (name "unconnected-(P3-PAD-Pad7)") (class "Default")
      (node (ref "P3") (pin "7") (pinfunction "PAD_7") (pintype "passive+no_connect"))
    )
    (net (code "77") (name "unconnected-(X2-NC-Pad7)") (class "Default")
      (node (ref "X2") (pin "7") (pinfunction "NC_7") (pintype "passive+no_connect"))
    )
    (net (code "78") (name "unconnected-(X2-NC-Pad13)") (class "Default")
      (node (ref "X2") (pin "13") (pinfunction "NC_13") (pintype "passive+no_connect"))
    )
    (net (code "79") (name "unconnected-(X2-NC-Pad15)") (class "Default")
      (node (ref "X2") (pin "15") (pinfunction "NC_15") (pintype "passive+no_connect"))
    )
  )
)
